# Bpod_Serial_Shield_r1.net
KiCad netlist of a schematic drawn in EAGLE
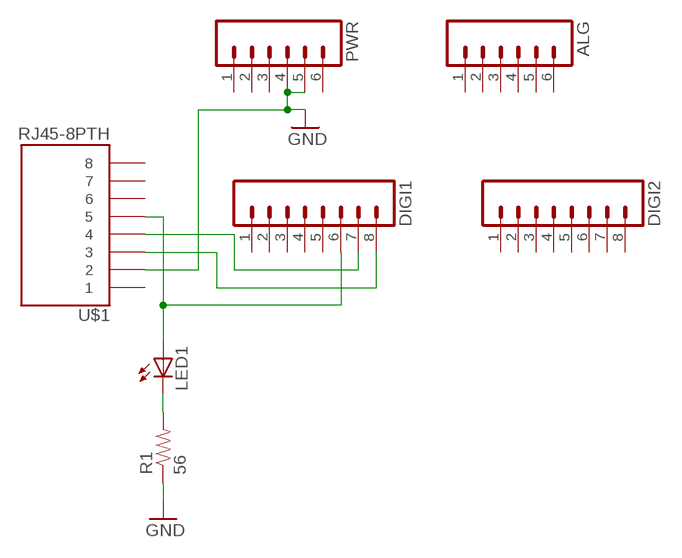
[diagram p0: schematic, sheet 1]

(export (version "E")
  (design (tool "Eeschema 10.0.6"))
  (components
    (comp (ref "ALG")
      (value "M06LONGPADS")
      (footprint "eagle-import:1X06_LONGPADS")
      (libsource (lib "eagle-import") (part "M06LONGPADS"))
    )
    (comp (ref "DIGI1")
      (value "M08LONGPADS")
      (footprint "eagle-import:1X08_LONGPADS")
      (libsource (lib "eagle-import") (part "M08LONGPADS"))
    )
    (comp (ref "DIGI2")
      (value "M08LONGPADS")
      (footprint "eagle-import:1X08_LONGPADS")
      (libsource (lib "eagle-import") (part "M08LONGPADS"))
    )
    (comp (ref "LED1")
      (value "LED3MM")
      (footprint "eagle-import:LED3MM")
      (libsource (lib "eagle-import") (part "LED3MM"))
    )
    (comp (ref "PWR")
      (value "M06LONGPADS")
      (footprint "eagle-import:1X06_LONGPADS")
      (libsource (lib "eagle-import") (part "M06LONGPADS"))
    )
    (comp (ref "R1")
      (value "56")
      (footprint "eagle-import:AXIAL-0.3")
      (libsource (lib "eagle-import") (part "RESISTORAXIAL-0.3"))
    )
    (comp (ref "U$1")
      (value "RJ45-8PTH")
      (footprint "eagle-import:RJ45-8")
      (libsource (lib "eagle-import") (part "RJ45-8PTH"))
    )
  )
  (nets
    (net (code "1") (name "GND") (class "Default")
      (node (ref "PWR") (pin "4") (pinfunction "4_4") (pintype "passive"))
      (node (ref "PWR") (pin "5") (pinfunction "5_5") (pintype "passive"))
      (node (ref "R1") (pin "P$1") (pinfunction "1_P$1") (pintype "passive"))
      (node (ref "U$1") (pin "2") (pinfunction "2_2") (pintype "bidirectional"))
    )
    (net (code "2") (name "Net-(DIGI1-Pad6)") (class "Default")
      (node (ref "DIGI1") (pin "6") (pinfunction "6_6") (pintype "passive"))
      (node (ref "LED1") (pin "A") (pinfunction "A_A") (pintype "passive"))
      (node (ref "U$1") (pin "5") (pinfunction "5_5") (pintype "bidirectional"))
    )
    (net (code "3") (name "Net-(DIGI1-Pad7)") (class "Default")
      (node (ref "DIGI1") (pin "7") (pinfunction "7_7") (pintype "passive"))
      (node (ref "U$1") (pin "4") (pinfunction "4_4") (pintype "bidirectional"))
    )
    (net (code "4") (name "Net-(DIGI1-Pad8)") (class "Default")
      (node (ref "DIGI1") (pin "8") (pinfunction "8_8") (pintype "passive"))
      (node (ref "U$1") (pin "3") (pinfunction "3_3") (pintype "bidirectional"))
    )
    (net (code "5") (name "Net-(LED1-C)") (class "Default")
      (node (ref "LED1") (pin "K") (pinfunction "C_K") (pintype "passive"))
      (node (ref "R1") (pin "P$2") (pinfunction "2_P$2") (pintype "passive"))
    )
    (net (code "6") (name "unconnected-(ALG-Pad1)") (class "Default")
      (node (ref "ALG") (pin "1") (pinfunction "1_1") (pintype "passive"))
    )
    (net (code "7") (name "unconnected-(ALG-Pad2)") (class "Default")
      (node (ref "ALG") (pin "2") (pinfunction "2_2") (pintype "passive"))
    )
    (net (code "8") (name "unconnected-(ALG-Pad3)") (class "Default")
      (node (ref "ALG") (pin "3") (pinfunction "3_3") (pintype "passive"))
    )
    (net (code "9") (name "unconnected-(ALG-Pad4)") (class "Default")
      (node (ref "ALG") (pin "4") (pinfunction "4_4") (pintype "passive"))
    )
    (net (code "10") (name "unconnected-(ALG-Pad5)") (class "Default")
      (node (ref "ALG") (pin "5") (pinfunction "5_5") (pintype "passive"))
    )
    (net (code "11") (name "unconnected-(ALG-Pad6)") (class "Default")
      (node (ref "ALG") (pin "6") (pinfunction "6_6") (pintype "passive"))
    )
    (net (code "12") (name "unconnected-(DIGI1-Pad1)") (class "Default")
      (node (ref "DIGI1") (pin "1") (pinfunction "1_1") (pintype "passive"))
    )
    (net (code "13") (name "unconnected-(DIGI1-Pad2)") (class "Default")
      (node (ref "DIGI1") (pin "2") (pinfunction "2_2") (pintype "passive"))
    )
    (net (code "14") (name "unconnected-(DIGI1-Pad3)") (class "Default")
      (node (ref "DIGI1") (pin "3") (pinfunction "3_3") (pintype "passive"))
    )
    (net (code "15") (name "unconnected-(DIGI1-Pad4)") (class "Default")
      (node (ref "DIGI1") (pin "4") (pinfunction "4_4") (pintype "passive"))
    )
    (net (code "16") (name "unconnected-(DIGI1-Pad5)") (class "Default")
      (node (ref "DIGI1") (pin "5") (pinfunction "5_5") (pintype "passive"))
    )
    (net (code "17") (name "unconnected-(DIGI2-Pad1)") (class "Default")
      (node (ref "DIGI2") (pin "1") (pinfunction "1_1") (pintype "passive"))
    )
    (net (code "18") (name "unconnected-(DIGI2-Pad2)") (class "Default")
      (node (ref "DIGI2") (pin "2") (pinfunction "2_2") (pintype "passive"))
    )
    (net (code "19") (name "unconnected-(DIGI2-Pad3)") (class "Default")
      (node (ref "DIGI2") (pin "3") (pinfunction "3_3") (pintype "passive"))
    )
    (net (code "20") (name "unconnected-(DIGI2-Pad4)") (class "Default")
      (node (ref "DIGI2") (pin "4") (pinfunction "4_4") (pintype "passive"))
    )
    (net (code "21") (name "unconnected-(DIGI2-Pad5)") (class "Default")
      (node (ref "DIGI2") (pin "5") (pinfunction "5_5") (pintype "passive"))
    )
    (net (code "22") (name "unconnected-(DIGI2-Pad6)") (class "Default")
      (node (ref "DIGI2") (pin "6") (pinfunction "6_6") (pintype "passive"))
    )
    (net (code "23") (name "unconnected-(DIGI2-Pad7)") (class "Default")
      (node (ref "DIGI2") (pin "7") (pinfunction "7_7") (pintype "passive"))
    )
    (net (code "24") (name "unconnected-(DIGI2-Pad8)") (class "Default")
      (node (ref "DIGI2") (pin "8") (pinfunction "8_8") (pintype "passive"))
    )
    (net (code "25") (name "unconnected-(PWR-Pad1)") (class "Default")
      (node (ref "PWR") (pin "1") (pinfunction "1_1") (pintype "passive"))
    )
    (net (code "26") (name "unconnected-(PWR-Pad2)") (class "Default")
      (node (ref "PWR") (pin "2") (pinfunction "2_2") (pintype "passive"))
    )
    (net (code "27") (name "unconnected-(PWR-Pad3)") (class "Default")
      (node (ref "PWR") (pin "3") (pinfunction "3_3") (pintype "passive"))
    )
    (net (code "28") (name "unconnected-(PWR-Pad6)") (class "Default")
      (node (ref "PWR") (pin "6") (pinfunction "6_6") (pintype "passive"))
    )
    (net (code "29") (name "unconnected-(U$1-Pad1)") (class "Default")
      (node (ref "U$1") (pin "1") (pinfunction "1_1") (pintype "bidirectional"))
    )
    (net (code "30") (name "unconnected-(U$1-Pad6)") (class "Default")
      (node (ref "U$1") (pin "6") (pinfunction "6_6") (pintype "bidirectional"))
    )
    (net (code "31") (name "unconnected-(U$1-Pad7)") (class "Default")
      (node (ref "U$1") (pin "7") (pinfunction "7_7") (pintype "bidirectional"))
    )
    (net (code "32") (name "unconnected-(U$1-Pad8)") (class "Default")
      (node (ref "U$1") (pin "8") (pinfunction "8_8") (pintype "bidirectional"))
    )
  )
)
